# mutteruhr-Haus.net
KiCad netlist of a schematic drawn in EAGLE
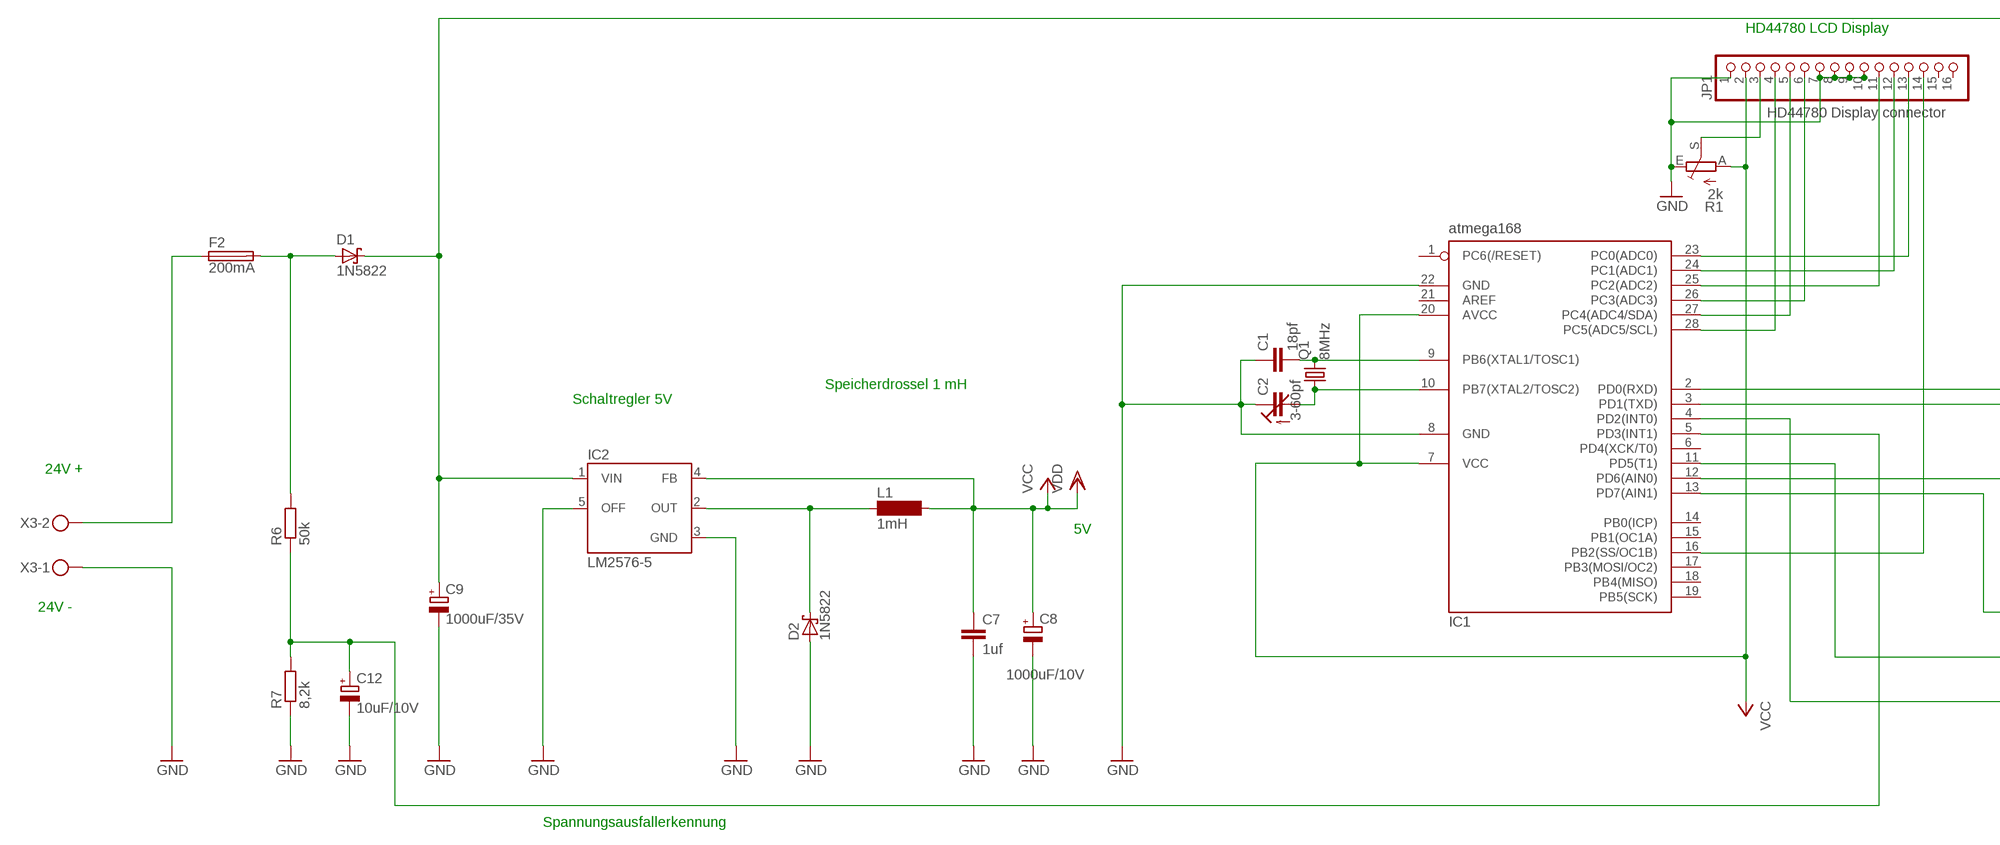
[diagram p0: schematic, sheet 1, part 1 of 2]
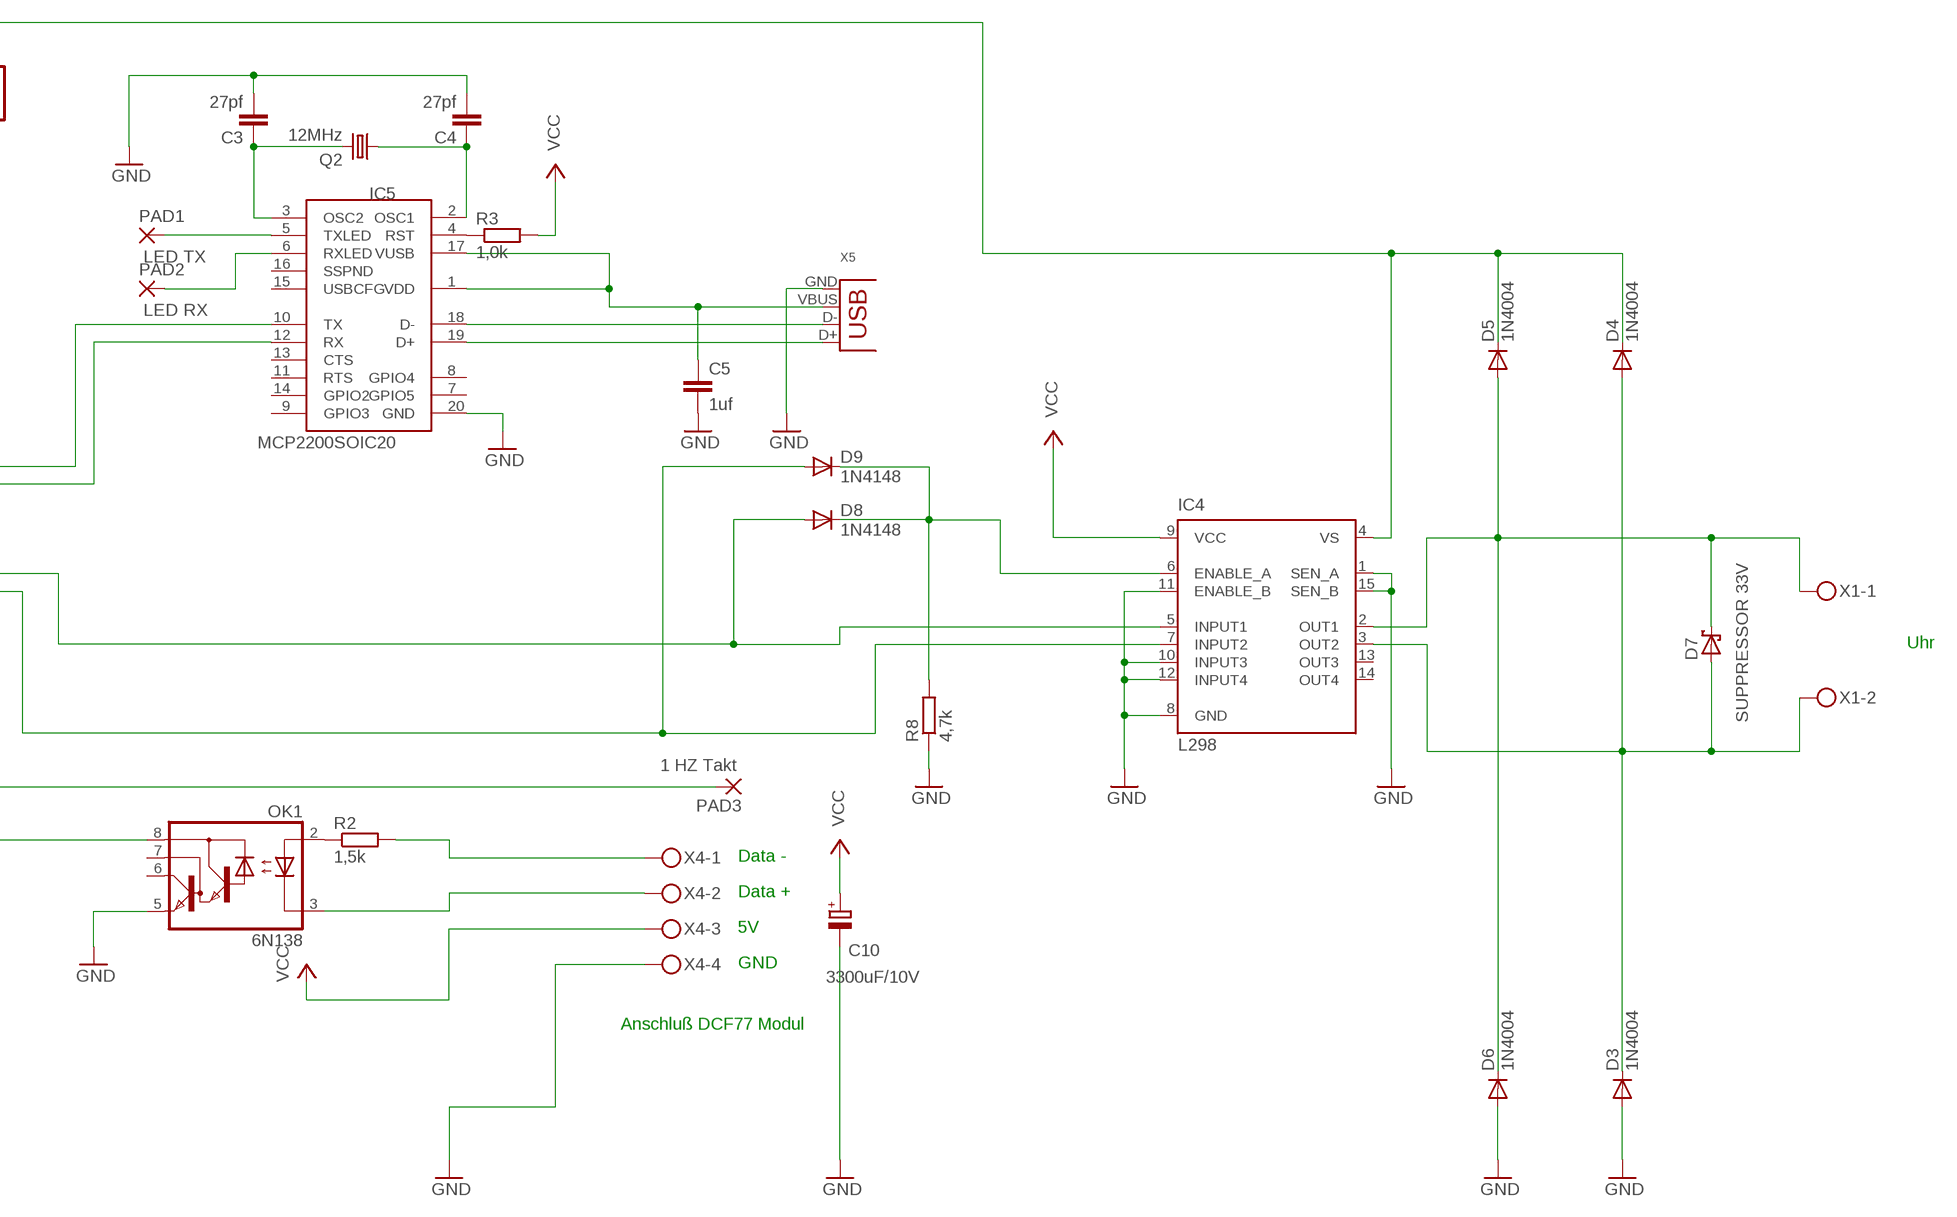
[diagram p1: schematic, sheet 1, part 2 of 2]

(export (version "E")
  (design (tool "Eeschema 10.0.6"))
  (components
    (comp (ref "C1")
      (value "18pf")
      (footprint "eagle-import:C050-024X044")
      (libsource (lib "eagle-import") (part "C-EU050-024X044"))
    )
    (comp (ref "C2")
      (value "3-60pf")
      (footprint "eagle-import:CTRIM3050.505")
      (libsource (lib "eagle-import") (part "C-TRIMM3050.505"))
    )
    (comp (ref "C3")
      (value "27pf")
      (footprint "eagle-import:C050-024X044")
      (libsource (lib "eagle-import") (part "C-EU050-024X044"))
    )
    (comp (ref "C4")
      (value "27pf")
      (footprint "eagle-import:C050-024X044")
      (libsource (lib "eagle-import") (part "C-EU050-024X044"))
    )
    (comp (ref "C5")
      (value "1uf")
      (footprint "eagle-import:C5B5.5")
      (libsource (lib "eagle-import") (part "C5/5.5"))
    )
    (comp (ref "C7")
      (value "1uf")
      (footprint "eagle-import:C5B5.5")
      (libsource (lib "eagle-import") (part "C5/5.5"))
    )
    (comp (ref "C8")
      (value "1000uF/10V")
      (footprint "eagle-import:E5-8,5")
      (libsource (lib "eagle-import") (part "CPOL-EUE5-8.5"))
    )
    (comp (ref "C9")
      (value "1000uF/35V")
      (footprint "eagle-import:E5-8,5")
      (libsource (lib "eagle-import") (part "CPOL-EUE5-8.5"))
    )
    (comp (ref "C10")
      (value "3300uF/10V")
      (footprint "eagle-import:E7,5-16")
      (libsource (lib "eagle-import") (part "CPOL-EUE7.5-16"))
    )
    (comp (ref "C12")
      (value "10uF/10V")
      (footprint "eagle-import:E5-5")
      (libsource (lib "eagle-import") (part "rcl-2_CPOL-EUE5-5"))
    )
    (comp (ref "D1")
      (value "1N5822")
      (footprint "eagle-import:DO41-7.6")
      (libsource (lib "eagle-import") (part "1N5819-B"))
    )
    (comp (ref "D2")
      (value "1N5822")
      (footprint "eagle-import:DO41-7.6")
      (libsource (lib "eagle-import") (part "1N5819-B"))
    )
    (comp (ref "D3")
      (value "1N4004")
      (footprint "eagle-import:DO41-10")
      (libsource (lib "eagle-import") (part "1N4004"))
    )
    (comp (ref "D4")
      (value "1N4004")
      (footprint "eagle-import:DO41-10")
      (libsource (lib "eagle-import") (part "1N4004"))
    )
    (comp (ref "D5")
      (value "1N4004")
      (footprint "eagle-import:DO41-10")
      (libsource (lib "eagle-import") (part "1N4004"))
    )
    (comp (ref "D6")
      (value "1N4004")
      (footprint "eagle-import:DO41-10")
      (libsource (lib "eagle-import") (part "1N4004"))
    )
    (comp (ref "D7")
      (value "SUPPRESSOR 33V")
      (footprint "eagle-import:DO41-10")
      (libsource (lib "eagle-import") (part "P4KEXX"))
    )
    (comp (ref "D8")
      (value "1N4148")
      (footprint "eagle-import:DO35-7")
      (libsource (lib "eagle-import") (part "1N4148DO35-7"))
    )
    (comp (ref "D9")
      (value "1N4148")
      (footprint "eagle-import:DO35-7")
      (libsource (lib "eagle-import") (part "1N4148DO35-7"))
    )
    (comp (ref "F2")
      (value "200mA")
      (footprint "eagle-import:SH25")
      (fields (field (name "MF") "SCHURTER") (field (name "MPN") "0031.8211"))
      (libsource (lib "eagle-import") (part "SH25"))
    )
    (comp (ref "IC1")
      (value "atmega168")
      (footprint "eagle-import:DIL28-3")
      (libsource (lib "eagle-import") (part "MEGA8-P"))
    )
    (comp (ref "IC2")
      (value "LM2576-5")
      (footprint "eagle-import:TO220-5")
      (libsource (lib "eagle-import") (part "LM2576T"))
    )
    (comp (ref "IC4")
      (value "L298")
      (footprint "eagle-import:MULTIWATT-15")
      (fields (field (name "MPN") "L298N"))
      (libsource (lib "eagle-import") (part "L298"))
    )
    (comp (ref "IC5")
      (value "MCP2200SOIC20")
      (footprint "eagle-import:SOIC20")
      (libsource (lib "eagle-import") (part "MCP2200SOIC20"))
    )
    (comp (ref "JP1")
      (value "HD44780 Display connector")
      (footprint "eagle-import:1X16")
      (libsource (lib "eagle-import") (part "PINHD-1X16_2.54"))
    )
    (comp (ref "L1")
      (value "1mH")
      (footprint "eagle-import:BS11")
      (libsource (lib "eagle-import") (part "BS11"))
    )
    (comp (ref "OK1")
      (value "6N138")
      (footprint "eagle-import:DIL08")
      (fields (field (name "MF") "VISHAY/TELEFUNKEN"))
      (libsource (lib "eagle-import") (part "6N138"))
    )
    (comp (ref "PAD1")
      (value "LED TX")
      (footprint "eagle-import:2,54_0,8")
      (libsource (lib "eagle-import") (part "2,54/0,8"))
    )
    (comp (ref "PAD2")
      (value "LED RX")
      (footprint "eagle-import:2,54_0,8")
      (libsource (lib "eagle-import") (part "2,54/0,8"))
    )
    (comp (ref "PAD3")
      (value "1 HZ Takt")
      (footprint "eagle-import:2,54_0,8")
      (libsource (lib "eagle-import") (part "2,54/0,8"))
    )
    (comp (ref "Q1")
      (value "8MHz")
      (footprint "eagle-import:HC18U-V")
      (libsource (lib "eagle-import") (part "CRYSTALHC18U-V"))
    )
    (comp (ref "Q2")
      (value "12MHz")
      (footprint "eagle-import:HC18U-V")
      (libsource (lib "eagle-import") (part "CRYSTALHC18U-V"))
    )
    (comp (ref "R1")
      (value "2k")
      (footprint "eagle-import:RS3")
      (libsource (lib "eagle-import") (part "TRIM_EU-RS3"))
    )
    (comp (ref "R2")
      (value "1,5k")
      (footprint "eagle-import:0207_10")
      (libsource (lib "eagle-import") (part "R-EU_0207/10"))
    )
    (comp (ref "R3")
      (value "1,0k")
      (footprint "eagle-import:0207_10")
      (libsource (lib "eagle-import") (part "R-EU_0207/10"))
    )
    (comp (ref "R6")
      (value "50k")
      (footprint "eagle-import:0207_10")
      (libsource (lib "eagle-import") (part "R-EU_0207/10"))
    )
    (comp (ref "R7")
      (value "8,2k")
      (footprint "eagle-import:0207_10")
      (libsource (lib "eagle-import") (part "R-EU_0207/10"))
    )
    (comp (ref "R8")
      (value "4,7k")
      (footprint "eagle-import:0207_10")
      (libsource (lib "eagle-import") (part "R-EU_0207/10"))
    )
    (comp (ref "X1")
      (value "MKDSN1,5/2-5,08")
      (footprint "eagle-import:MKDSN1,5_2-5,08")
      (fields (field (name "MPN") "MKDSN 1,5/2-5.08"))
      (libsource (lib "eagle-import") (part "MKDSN1,5/2-5,08"))
    )
    (comp (ref "X3")
      (value "MKDSN1,5/2-5,08")
      (footprint "eagle-import:MKDSN1,5_2-5,08")
      (fields (field (name "MPN") "MKDSN 1,5/2-5.08"))
      (libsource (lib "eagle-import") (part "MKDSN1,5/2-5,08"))
    )
    (comp (ref "X4")
      (value "MKDSN1,5/4-5,08")
      (footprint "eagle-import:MKDSN1,5_4-5,08")
      (fields (field (name "MPN") "SMKDSN1,5/4-5,08"))
      (libsource (lib "eagle-import") (part "MKDSN1,5/4-5,08"))
    )
    (comp (ref "X5")
      (value "USB-B-H")
      (footprint "eagle-import:USB-B-H")
      (libsource (lib "eagle-import") (part "USB-B-H"))
    )
  )
  (nets
    (net (code "1") (name "GND") (class "Default")
      (node (ref "C1") (pin "1") (pinfunction "1_1") (pintype "passive"))
      (node (ref "C10") (pin "-") (pinfunction "-_-") (pintype "passive"))
      (node (ref "C12") (pin "-") (pinfunction "-_-") (pintype "passive"))
      (node (ref "C2") (pin "1") (pinfunction "E_1") (pintype "passive"))
      (node (ref "C3") (pin "2") (pinfunction "2_2") (pintype "passive"))
      (node (ref "C4") (pin "2") (pinfunction "2_2") (pintype "passive"))
      (node (ref "C5") (pin "2") (pinfunction "2_2") (pintype "passive"))
      (node (ref "C7") (pin "2") (pinfunction "2_2") (pintype "passive"))
      (node (ref "C8") (pin "-") (pinfunction "-_-") (pintype "passive"))
      (node (ref "C9") (pin "-") (pinfunction "-_-") (pintype "passive"))
      (node (ref "D2") (pin "A") (pinfunction "A_A") (pintype "passive"))
      (node (ref "D3") (pin "A") (pinfunction "A_A") (pintype "passive"))
      (node (ref "D6") (pin "A") (pinfunction "A_A") (pintype "passive"))
      (node (ref "IC1") (pin "22") (pinfunction "GND_22") (pintype "power_in"))
      (node (ref "IC1") (pin "8") (pinfunction "GND_8") (pintype "power_in"))
      (node (ref "IC2") (pin "3") (pinfunction "GND_3") (pintype "power_in"))
      (node (ref "IC2") (pin "5") (pinfunction "OFF_5") (pintype "input"))
      (node (ref "IC4") (pin "1") (pinfunction "SEN_A_1") (pintype "input"))
      (node (ref "IC4") (pin "10") (pinfunction "INPUT3_10") (pintype "input"))
      (node (ref "IC4") (pin "11") (pinfunction "ENABLE_B_11") (pintype "input"))
      (node (ref "IC4") (pin "12") (pinfunction "INPUT4_12") (pintype "input"))
      (node (ref "IC4") (pin "15") (pinfunction "SEN_B_15") (pintype "input"))
      (node (ref "IC4") (pin "8") (pinfunction "GND_8") (pintype "power_in"))
      (node (ref "IC5") (pin "20") (pinfunction "GND_20") (pintype "bidirectional"))
      (node (ref "JP1") (pin "1") (pinfunction "1_1") (pintype "passive"))
      (node (ref "JP1") (pin "10") (pinfunction "10_10") (pintype "passive"))
      (node (ref "JP1") (pin "7") (pinfunction "7_7") (pintype "passive"))
      (node (ref "JP1") (pin "8") (pinfunction "8_8") (pintype "passive"))
      (node (ref "JP1") (pin "9") (pinfunction "9_9") (pintype "passive"))
      (node (ref "OK1") (pin "5") (pinfunction "GND_5") (pintype "passive"))
      (node (ref "R1") (pin "E") (pinfunction "E_E") (pintype "passive"))
      (node (ref "R7") (pin "1") (pinfunction "1_1") (pintype "passive"))
      (node (ref "R8") (pin "1") (pinfunction "1_1") (pintype "passive"))
      (node (ref "X3") (pin "1") (pinfunction "KL_1") (pintype "passive"))
      (node (ref "X4") (pin "4") (pinfunction "KL_4") (pintype "passive"))
      (node (ref "X5") (pin "GND") (pinfunction "GND_GND") (pintype "bidirectional"))
    )
    (net (code "2") (name "Net-(C2-A)") (class "Default")
      (node (ref "C2") (pin "2") (pinfunction "A_2") (pintype "passive"))
      (node (ref "IC1") (pin "10") (pinfunction "PB7(XTAL2/TOSC2)_10") (pintype "bidirectional"))
      (node (ref "Q1") (pin "1") (pinfunction "1_1") (pintype "passive"))
    )
    (net (code "3") (name "Net-(D1-PadA)") (class "Default")
      (node (ref "D1") (pin "A") (pinfunction "A_A") (pintype "passive"))
      (node (ref "F2") (pin "2") (pinfunction "2_2") (pintype "passive"))
      (node (ref "R6") (pin "2") (pinfunction "2_2") (pintype "passive"))
    )
    (net (code "4") (name "Net-(IC1-PB2(SS{slash}OC1B))") (class "Default")
      (node (ref "IC1") (pin "16") (pinfunction "PB2(SS/OC1B)_16") (pintype "bidirectional"))
      (node (ref "JP1") (pin "14") (pinfunction "14_14") (pintype "passive"))
    )
    (net (code "5") (name "Net-(IC1-PB6(XTAL1{slash}TOSC1))") (class "Default")
      (node (ref "C1") (pin "2") (pinfunction "2_2") (pintype "passive"))
      (node (ref "IC1") (pin "9") (pinfunction "PB6(XTAL1/TOSC1)_9") (pintype "bidirectional"))
      (node (ref "Q1") (pin "2") (pinfunction "2_2") (pintype "passive"))
    )
    (net (code "6") (name "Net-(IC1-PC0(ADC0))") (class "Default")
      (node (ref "IC1") (pin "23") (pinfunction "PC0(ADC0)_23") (pintype "bidirectional"))
      (node (ref "JP1") (pin "13") (pinfunction "13_13") (pintype "passive"))
    )
    (net (code "7") (name "Net-(IC1-PC1(ADC1))") (class "Default")
      (node (ref "IC1") (pin "24") (pinfunction "PC1(ADC1)_24") (pintype "bidirectional"))
      (node (ref "JP1") (pin "12") (pinfunction "12_12") (pintype "passive"))
    )
    (net (code "8") (name "Net-(IC1-PC2(ADC2))") (class "Default")
      (node (ref "IC1") (pin "25") (pinfunction "PC2(ADC2)_25") (pintype "bidirectional"))
      (node (ref "JP1") (pin "11") (pinfunction "11_11") (pintype "passive"))
    )
    (net (code "9") (name "Net-(IC1-PC3(ADC3))") (class "Default")
      (node (ref "IC1") (pin "26") (pinfunction "PC3(ADC3)_26") (pintype "bidirectional"))
      (node (ref "JP1") (pin "6") (pinfunction "6_6") (pintype "passive"))
    )
    (net (code "10") (name "Net-(IC1-PC4(ADC4{slash}SDA))") (class "Default")
      (node (ref "IC1") (pin "27") (pinfunction "PC4(ADC4/SDA)_27") (pintype "bidirectional"))
      (node (ref "JP1") (pin "5") (pinfunction "5_5") (pintype "passive"))
    )
    (net (code "11") (name "Net-(IC1-PC5(ADC5{slash}SCL))") (class "Default")
      (node (ref "IC1") (pin "28") (pinfunction "PC5(ADC5/SCL)_28") (pintype "bidirectional"))
      (node (ref "JP1") (pin "4") (pinfunction "4_4") (pintype "passive"))
    )
    (net (code "12") (name "Net-(IC1-PD0(RXD))") (class "Default")
      (node (ref "IC1") (pin "2") (pinfunction "PD0(RXD)_2") (pintype "bidirectional"))
      (node (ref "IC5") (pin "10") (pinfunction "TX_10") (pintype "bidirectional"))
    )
    (net (code "13") (name "Net-(IC1-PD1(TXD))") (class "Default")
      (node (ref "IC1") (pin "3") (pinfunction "PD1(TXD)_3") (pintype "bidirectional"))
      (node (ref "IC5") (pin "12") (pinfunction "RX_12") (pintype "bidirectional"))
    )
    (net (code "14") (name "Net-(IC1-PD2(INT0))") (class "Default")
      (node (ref "IC1") (pin "4") (pinfunction "PD2(INT0)_4") (pintype "bidirectional"))
      (node (ref "OK1") (pin "8") (pinfunction "VCC_8") (pintype "passive"))
    )
    (net (code "15") (name "Net-(IC1-PD3(INT1))") (class "Default")
      (node (ref "C12") (pin "+") (pinfunction "+_+") (pintype "passive"))
      (node (ref "IC1") (pin "5") (pinfunction "PD3(INT1)_5") (pintype "bidirectional"))
      (node (ref "R6") (pin "1") (pinfunction "1_1") (pintype "passive"))
      (node (ref "R7") (pin "2") (pinfunction "2_2") (pintype "passive"))
    )
    (net (code "16") (name "Net-(IC1-PD5(T1))") (class "Default")
      (node (ref "IC1") (pin "11") (pinfunction "PD5(T1)_11") (pintype "bidirectional"))
      (node (ref "PAD3") (pin "1") (pinfunction "P_1") (pintype "passive"))
    )
    (net (code "17") (name "Net-(IC1-PD6(AIN0))") (class "Default")
      (node (ref "D8") (pin "A") (pinfunction "A_A") (pintype "passive"))
      (node (ref "IC1") (pin "12") (pinfunction "PD6(AIN0)_12") (pintype "bidirectional"))
      (node (ref "IC4") (pin "5") (pinfunction "INPUT1_5") (pintype "input"))
    )
    (net (code "18") (name "Net-(IC1-PD7(AIN1))") (class "Default")
      (node (ref "D9") (pin "A") (pinfunction "A_A") (pintype "passive"))
      (node (ref "IC1") (pin "13") (pinfunction "PD7(AIN1)_13") (pintype "bidirectional"))
      (node (ref "IC4") (pin "7") (pinfunction "INPUT2_7") (pintype "input"))
    )
    (net (code "19") (name "Net-(IC2-OUT)") (class "Default")
      (node (ref "D2") (pin "C") (pinfunction "C_C") (pintype "passive"))
      (node (ref "IC2") (pin "2") (pinfunction "OUT_2") (pintype "output"))
      (node (ref "L1") (pin "1") (pinfunction "1_1") (pintype "passive"))
    )
    (net (code "20") (name "Net-(IC2-VIN)") (class "Default")
      (node (ref "C9") (pin "+") (pinfunction "+_+") (pintype "passive"))
      (node (ref "D1") (pin "C") (pinfunction "C_C") (pintype "passive"))
      (node (ref "D4") (pin "C") (pinfunction "C_C") (pintype "passive"))
      (node (ref "D5") (pin "C") (pinfunction "C_C") (pintype "passive"))
      (node (ref "IC2") (pin "1") (pinfunction "VIN_1") (pintype "power_in"))
      (node (ref "IC4") (pin "4") (pinfunction "VS_4") (pintype "power_in"))
    )
    (net (code "21") (name "Net-(IC4-ENABLE_A)") (class "Default")
      (node (ref "D8") (pin "C") (pinfunction "C_C") (pintype "passive"))
      (node (ref "D9") (pin "C") (pinfunction "C_C") (pintype "passive"))
      (node (ref "IC4") (pin "6") (pinfunction "ENABLE_A_6") (pintype "input"))
      (node (ref "R8") (pin "2") (pinfunction "2_2") (pintype "passive"))
    )
    (net (code "22") (name "Net-(IC4-OUT1)") (class "Default")
      (node (ref "D5") (pin "A") (pinfunction "A_A") (pintype "passive"))
      (node (ref "D6") (pin "C") (pinfunction "C_C") (pintype "passive"))
      (node (ref "D7") (pin "C") (pinfunction "C_C") (pintype "passive"))
      (node (ref "IC4") (pin "2") (pinfunction "OUT1_2") (pintype "output"))
      (node (ref "X1") (pin "1") (pinfunction "KL_1") (pintype "passive"))
    )
    (net (code "23") (name "Net-(IC4-OUT2)") (class "Default")
      (node (ref "D3") (pin "C") (pinfunction "C_C") (pintype "passive"))
      (node (ref "D4") (pin "A") (pinfunction "A_A") (pintype "passive"))
      (node (ref "D7") (pin "A") (pinfunction "A_A") (pintype "passive"))
      (node (ref "IC4") (pin "3") (pinfunction "OUT2_3") (pintype "output"))
      (node (ref "X1") (pin "2") (pinfunction "KL_2") (pintype "passive"))
    )
    (net (code "24") (name "Net-(IC5-D+)") (class "Default")
      (node (ref "IC5") (pin "19") (pinfunction "D+_19") (pintype "bidirectional"))
      (node (ref "X5") (pin "D+") (pinfunction "D+_D+") (pintype "bidirectional"))
    )
    (net (code "25") (name "Net-(IC5-D-)") (class "Default")
      (node (ref "IC5") (pin "18") (pinfunction "D-_18") (pintype "bidirectional"))
      (node (ref "X5") (pin "D-") (pinfunction "D-_D-") (pintype "bidirectional"))
    )
    (net (code "26") (name "Net-(IC5-OSC1)") (class "Default")
      (node (ref "C4") (pin "1") (pinfunction "1_1") (pintype "passive"))
      (node (ref "IC5") (pin "2") (pinfunction "OSC1_2") (pintype "bidirectional"))
      (node (ref "Q2") (pin "1") (pinfunction "1_1") (pintype "passive"))
    )
    (net (code "27") (name "Net-(IC5-OSC2)") (class "Default")
      (node (ref "C3") (pin "1") (pinfunction "1_1") (pintype "passive"))
      (node (ref "IC5") (pin "3") (pinfunction "OSC2_3") (pintype "bidirectional"))
      (node (ref "Q2") (pin "2") (pinfunction "2_2") (pintype "passive"))
    )
    (net (code "28") (name "Net-(IC5-RST)") (class "Default")
      (node (ref "IC5") (pin "4") (pinfunction "RST_4") (pintype "bidirectional"))
      (node (ref "R3") (pin "1") (pinfunction "1_1") (pintype "passive"))
    )
    (net (code "29") (name "Net-(IC5-RXLED)") (class "Default")
      (node (ref "IC5") (pin "6") (pinfunction "RXLED_6") (pintype "bidirectional"))
      (node (ref "PAD2") (pin "1") (pinfunction "P_1") (pintype "passive"))
    )
    (net (code "30") (name "Net-(IC5-TXLED)") (class "Default")
      (node (ref "IC5") (pin "5") (pinfunction "TXLED_5") (pintype "bidirectional"))
      (node (ref "PAD1") (pin "1") (pinfunction "P_1") (pintype "passive"))
    )
    (net (code "31") (name "Net-(IC5-VDD)") (class "Default")
      (node (ref "C5") (pin "1") (pinfunction "1_1") (pintype "passive"))
      (node (ref "IC5") (pin "1") (pinfunction "VDD_1") (pintype "bidirectional"))
      (node (ref "IC5") (pin "17") (pinfunction "VUSB_17") (pintype "bidirectional"))
      (node (ref "X5") (pin "VBUS") (pinfunction "VBUS_VBUS") (pintype "bidirectional"))
    )
    (net (code "32") (name "Net-(JP1-Pad3)") (class "Default")
      (node (ref "JP1") (pin "3") (pinfunction "3_3") (pintype "passive"))
      (node (ref "R1") (pin "S") (pinfunction "S_S") (pintype "passive"))
    )
    (net (code "33") (name "Net-(OK1-A)") (class "Default")
      (node (ref "OK1") (pin "2") (pinfunction "A_2") (pintype "passive"))
      (node (ref "R2") (pin "1") (pinfunction "1_1") (pintype "passive"))
    )
    (net (code "34") (name "Net-(OK1-C)") (class "Default")
      (node (ref "OK1") (pin "3") (pinfunction "C_3") (pintype "passive"))
      (node (ref "X4") (pin "2") (pinfunction "KL_2") (pintype "passive"))
    )
    (net (code "35") (name "Net-(X3B-KL)") (class "Default")
      (node (ref "F2") (pin "1") (pinfunction "1_1") (pintype "passive"))
      (node (ref "X3") (pin "2") (pinfunction "KL_2") (pintype "passive"))
    )
    (net (code "36") (name "Net-(X4A-KL)") (class "Default")
      (node (ref "R2") (pin "2") (pinfunction "2_2") (pintype "passive"))
      (node (ref "X4") (pin "1") (pinfunction "KL_1") (pintype "passive"))
    )
    (net (code "37") (name "VCC") (class "Default")
      (node (ref "C10") (pin "+") (pinfunction "+_+") (pintype "passive"))
      (node (ref "C7") (pin "1") (pinfunction "1_1") (pintype "passive"))
      (node (ref "C8") (pin "+") (pinfunction "+_+") (pintype "passive"))
      (node (ref "IC1") (pin "20") (pinfunction "AVCC_20") (pintype "power_in"))
      (node (ref "IC1") (pin "7") (pinfunction "VCC_7") (pintype "power_in"))
      (node (ref "IC2") (pin "4") (pinfunction "FB_4") (pintype "input"))
      (node (ref "IC4") (pin "9") (pinfunction "VCC_9") (pintype "power_in"))
      (node (ref "JP1") (pin "2") (pinfunction "2_2") (pintype "passive"))
      (node (ref "L1") (pin "2") (pinfunction "2_2") (pintype "passive"))
      (node (ref "R1") (pin "A") (pinfunction "A_A") (pintype "passive"))
      (node (ref "R3") (pin "2") (pinfunction "2_2") (pintype "passive"))
      (node (ref "X4") (pin "3") (pinfunction "KL_3") (pintype "passive"))
    )
    (net (code "38") (name "unconnected-(IC1-AREF-Pad21)") (class "Default")
      (node (ref "IC1") (pin "21") (pinfunction "AREF_21") (pintype "passive"))
    )
    (net (code "39") (name "unconnected-(IC1-PB0(ICP)-Pad14)") (class "Default")
      (node (ref "IC1") (pin "14") (pinfunction "PB0(ICP)_14") (pintype "bidirectional"))
    )
    (net (code "40") (name "unconnected-(IC1-PB1(OC1A)-Pad15)") (class "Default")
      (node (ref "IC1") (pin "15") (pinfunction "PB1(OC1A)_15") (pintype "bidirectional"))
    )
    (net (code "41") (name "unconnected-(IC1-PB3(MOSI{slash}OC2)-Pad17)") (class "Default")
      (node (ref "IC1") (pin "17") (pinfunction "PB3(MOSI/OC2)_17") (pintype "bidirectional"))
    )
    (net (code "42") (name "unconnected-(IC1-PB4(MISO)-Pad18)") (class "Default")
      (node (ref "IC1") (pin "18") (pinfunction "PB4(MISO)_18") (pintype "bidirectional"))
    )
    (net (code "43") (name "unconnected-(IC1-PB5(SCK)-Pad19)") (class "Default")
      (node (ref "IC1") (pin "19") (pinfunction "PB5(SCK)_19") (pintype "bidirectional"))
    )
    (net (code "44") (name "unconnected-(IC1-PC6({slash}RESET)-Pad1)") (class "Default")
      (node (ref "IC1") (pin "1") (pinfunction "PC6(/RESET)_1") (pintype "bidirectional"))
    )
    (net (code "45") (name "unconnected-(IC1-PD4(XCK{slash}T0)-Pad6)") (class "Default")
      (node (ref "IC1") (pin "6") (pinfunction "PD4(XCK/T0)_6") (pintype "bidirectional"))
    )
    (net (code "46") (name "unconnected-(IC4-OUT3-Pad13)") (class "Default")
      (node (ref "IC4") (pin "13") (pinfunction "OUT3_13") (pintype "output"))
    )
    (net (code "47") (name "unconnected-(IC4-OUT4-Pad14)") (class "Default")
      (node (ref "IC4") (pin "14") (pinfunction "OUT4_14") (pintype "output"))
    )
    (net (code "48") (name "unconnected-(IC5-CTS-Pad13)") (class "Default")
      (node (ref "IC5") (pin "13") (pinfunction "CTS_13") (pintype "bidirectional"))
    )
    (net (code "49") (name "unconnected-(IC5-GPIO2-Pad14)") (class "Default")
      (node (ref "IC5") (pin "14") (pinfunction "GPIO2_14") (pintype "bidirectional"))
    )
    (net (code "50") (name "unconnected-(IC5-GPIO3-Pad9)") (class "Default")
      (node (ref "IC5") (pin "9") (pinfunction "GPIO3_9") (pintype "bidirectional"))
    )
    (net (code "51") (name "unconnected-(IC5-GPIO4-Pad8)") (class "Default")
      (node (ref "IC5") (pin "8") (pinfunction "GPIO4_8") (pintype "bidirectional"))
    )
    (net (code "52") (name "unconnected-(IC5-GPIO5-Pad7)") (class "Default")
      (node (ref "IC5") (pin "7") (pinfunction "GPIO5_7") (pintype "bidirectional"))
    )
    (net (code "53") (name "unconnected-(IC5-RTS-Pad11)") (class "Default")
      (node (ref "IC5") (pin "11") (pinfunction "RTS_11") (pintype "bidirectional"))
    )
    (net (code "54") (name "unconnected-(IC5-SSPND-Pad16)") (class "Default")
      (node (ref "IC5") (pin "16") (pinfunction "SSPND_16") (pintype "bidirectional"))
    )
    (net (code "55") (name "unconnected-(IC5-USBCFG-Pad15)") (class "Default")
      (node (ref "IC5") (pin "15") (pinfunction "USBCFG_15") (pintype "bidirectional"))
    )
    (net (code "56") (name "unconnected-(JP1-Pad15)") (class "Default")
      (node (ref "JP1") (pin "15") (pinfunction "15_15") (pintype "passive"))
    )
    (net (code "57") (name "unconnected-(JP1-Pad16)") (class "Default")
      (node (ref "JP1") (pin "16") (pinfunction "16_16") (pintype "passive"))
    )
    (net (code "58") (name "unconnected-(OK1-VB-Pad7)") (class "Default")
      (node (ref "OK1") (pin "7") (pinfunction "VB_7") (pintype "passive"))
    )
    (net (code "59") (name "unconnected-(OK1-VO-Pad6)") (class "Default")
      (node (ref "OK1") (pin "6") (pinfunction "VO_6") (pintype "passive"))
    )
  )
)
